# main.net
KiCad netlist of a schematic drawn in EAGLE
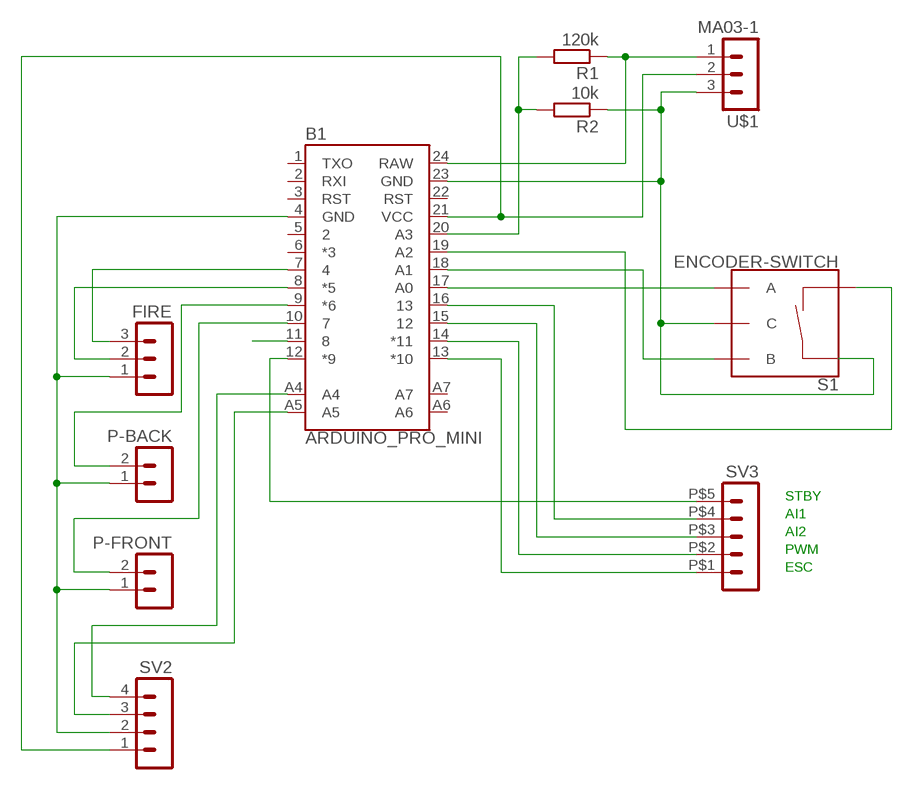
[diagram p0: schematic, sheet 1]

(export (version "E")
  (design (tool "Eeschema 10.0.6"))
  (components
    (comp (ref "B1")
      (value "ARDUINO_PRO_MINI")
      (footprint "eagle-import:ARDUINO_PRO_MINI_WO")
      (libsource (lib "eagle-import") (part "ARDUINO_PRO_MINI"))
    )
    (comp (ref "FIRE")
      (value "MA03-1")
      (footprint "eagle-import:MA03-1")
      (libsource (lib "eagle-import") (part "MA03-1"))
    )
    (comp (ref "P-BACK")
      (value "MA02-1")
      (footprint "eagle-import:MA02-1")
      (libsource (lib "eagle-import") (part "MA02-1"))
    )
    (comp (ref "P-FRONT")
      (value "MA02-1")
      (footprint "eagle-import:MA02-1")
      (libsource (lib "eagle-import") (part "MA02-1"))
    )
    (comp (ref "R1")
      (value "120k")
      (footprint "eagle-import:0204_5")
      (libsource (lib "eagle-import") (part "R-EU_0204/5"))
    )
    (comp (ref "R2")
      (value "10k")
      (footprint "eagle-import:0204V")
      (libsource (lib "eagle-import") (part "R-EU_0204/2V"))
    )
    (comp (ref "S1")
      (value "ENCODER-SWITCH")
      (footprint "eagle-import:ROTARY_ENC_PLAIN")
      (libsource (lib "eagle-import") (part "ENCODER-SWITCH"))
    )
    (comp (ref "SV2")
      (value "MA04-1")
      (footprint "eagle-import:MA04-1")
      (libsource (lib "eagle-import") (part "MA04-1"))
    )
    (comp (ref "SV3")
      (value "MA05-1")
      (footprint "eagle-import:MA05-1")
      (libsource (lib "eagle-import") (part "MA05-1"))
    )
    (comp (ref "U$1")
      (value "MA03-1")
      (footprint "eagle-import:MA03-1")
      (libsource (lib "eagle-import") (part "MA03-1"))
    )
  )
  (nets
    (net (code "1") (name "Net-(B1-*5)") (class "Default")
      (node (ref "B1") (pin "8") (pinfunction "*5_8") (pintype "bidirectional"))
      (node (ref "FIRE") (pin "2") (pinfunction "2_2") (pintype "passive"))
    )
    (net (code "2") (name "Net-(B1-*6)") (class "Default")
      (node (ref "B1") (pin "9") (pinfunction "*6_9") (pintype "bidirectional"))
      (node (ref "P-BACK") (pin "2") (pinfunction "3_2") (pintype "passive"))
    )
    (net (code "3") (name "Net-(B1-*9)") (class "Default")
      (node (ref "B1") (pin "12") (pinfunction "*9_12") (pintype "bidirectional"))
      (node (ref "SV3") (pin "P$5") (pinfunction "5_P$5") (pintype "passive"))
    )
    (net (code "4") (name "Net-(B1-*10)") (class "Default")
      (node (ref "B1") (pin "13") (pinfunction "*10_13") (pintype "bidirectional"))
      (node (ref "SV3") (pin "P$1") (pinfunction "1_P$1") (pintype "passive"))
    )
    (net (code "5") (name "Net-(B1-*11)") (class "Default")
      (node (ref "B1") (pin "14") (pinfunction "*11_14") (pintype "bidirectional"))
      (node (ref "SV3") (pin "P$2") (pinfunction "2_P$2") (pintype "passive"))
    )
    (net (code "6") (name "Net-(B1-4)") (class "Default")
      (node (ref "B1") (pin "7") (pinfunction "4_7") (pintype "bidirectional"))
      (node (ref "FIRE") (pin "3") (pinfunction "3_3") (pintype "passive"))
    )
    (net (code "7") (name "Net-(B1-7)") (class "Default")
      (node (ref "B1") (pin "10") (pinfunction "7_10") (pintype "bidirectional"))
      (node (ref "P-FRONT") (pin "2") (pinfunction "3_2") (pintype "passive"))
    )
    (net (code "8") (name "Net-(B1-12)") (class "Default")
      (node (ref "B1") (pin "15") (pinfunction "12_15") (pintype "bidirectional"))
      (node (ref "SV3") (pin "P$3") (pinfunction "3_P$3") (pintype "passive"))
    )
    (net (code "9") (name "Net-(B1-13)") (class "Default")
      (node (ref "B1") (pin "16") (pinfunction "13_16") (pintype "bidirectional"))
      (node (ref "SV3") (pin "P$4") (pinfunction "4_P$4") (pintype "passive"))
    )
    (net (code "10") (name "Net-(B1-A0)") (class "Default")
      (node (ref "B1") (pin "17") (pinfunction "A0_17") (pintype "bidirectional"))
      (node (ref "S1") (pin "A") (pinfunction "A_A") (pintype "bidirectional"))
    )
    (net (code "11") (name "Net-(B1-A1)") (class "Default")
      (node (ref "B1") (pin "18") (pinfunction "A1_18") (pintype "bidirectional"))
      (node (ref "S1") (pin "B") (pinfunction "B_B") (pintype "bidirectional"))
    )
    (net (code "12") (name "Net-(B1-A2)") (class "Default")
      (node (ref "B1") (pin "19") (pinfunction "A2_19") (pintype "bidirectional"))
      (node (ref "S1") (pin "SW-") (pinfunction "SW-_SW-") (pintype "bidirectional"))
    )
    (net (code "13") (name "Net-(B1-A3)") (class "Default")
      (node (ref "B1") (pin "20") (pinfunction "A3_20") (pintype "bidirectional"))
      (node (ref "R1") (pin "2") (pinfunction "2_2") (pintype "passive"))
      (node (ref "R2") (pin "2") (pinfunction "2_2") (pintype "passive"))
    )
    (net (code "14") (name "Net-(B1-GND-Pad23)") (class "Default")
      (node (ref "B1") (pin "23") (pinfunction "GND_23") (pintype "power_in"))
      (node (ref "R2") (pin "1") (pinfunction "1_1") (pintype "passive"))
      (node (ref "S1") (pin "C") (pinfunction "C_C") (pintype "bidirectional"))
      (node (ref "U$1") (pin "3") (pinfunction "3_3") (pintype "passive"))
    )
    (net (code "15") (name "Net-(B1-PadA4)") (class "Default")
      (node (ref "B1") (pin "A4") (pinfunction "A4_A4") (pintype "bidirectional"))
      (node (ref "SV2") (pin "4") (pinfunction "4_4") (pintype "passive"))
    )
    (net (code "16") (name "Net-(B1-PadA5)") (class "Default")
      (node (ref "B1") (pin "A5") (pinfunction "A5_A5") (pintype "bidirectional"))
      (node (ref "SV2") (pin "3") (pinfunction "3_3") (pintype "passive"))
    )
    (net (code "17") (name "Net-(B1-RAW)") (class "Default")
      (node (ref "B1") (pin "24") (pinfunction "RAW_24") (pintype "power_in"))
      (node (ref "R1") (pin "1") (pinfunction "1_1") (pintype "passive"))
      (node (ref "U$1") (pin "1") (pinfunction "1_1") (pintype "passive"))
    )
    (net (code "18") (name "Net-(B1-VCC)") (class "Default")
      (node (ref "B1") (pin "21") (pinfunction "VCC_21") (pintype "power_in"))
      (node (ref "SV2") (pin "1") (pinfunction "1_1") (pintype "passive"))
      (node (ref "U$1") (pin "2") (pinfunction "2_2") (pintype "passive"))
    )
    (net (code "19") (name "Net-(P-BACK-2)") (class "Default")
      (node (ref "B1") (pin "4") (pinfunction "GND_4") (pintype "power_in"))
      (node (ref "FIRE") (pin "1") (pinfunction "1_1") (pintype "passive"))
      (node (ref "P-BACK") (pin "1") (pinfunction "2_1") (pintype "passive"))
      (node (ref "P-FRONT") (pin "1") (pinfunction "2_1") (pintype "passive"))
      (node (ref "SV2") (pin "2") (pinfunction "2_2") (pintype "passive"))
    )
    (net (code "20") (name "unconnected-(B1-*3-Pad6)") (class "Default")
      (node (ref "B1") (pin "6") (pinfunction "*3_6") (pintype "bidirectional"))
    )
    (net (code "21") (name "unconnected-(B1-2-Pad5)") (class "Default")
      (node (ref "B1") (pin "5") (pinfunction "2_5") (pintype "bidirectional"))
    )
    (net (code "22") (name "unconnected-(B1-8-Pad11)") (class "Default")
      (node (ref "B1") (pin "11") (pinfunction "8_11") (pintype "bidirectional"))
    )
    (net (code "23") (name "unconnected-(B1-PadA6)") (class "Default")
      (node (ref "B1") (pin "A6") (pinfunction "A6_A6") (pintype "bidirectional"))
    )
    (net (code "24") (name "unconnected-(B1-PadA7)") (class "Default")
      (node (ref "B1") (pin "A7") (pinfunction "A7_A7") (pintype "bidirectional"))
    )
    (net (code "25") (name "unconnected-(B1-RST-Pad3)") (class "Default")
      (node (ref "B1") (pin "3") (pinfunction "RST_3") (pintype "bidirectional"))
    )
    (net (code "26") (name "unconnected-(B1-RST-Pad22)") (class "Default")
      (node (ref "B1") (pin "22") (pinfunction "RST_22") (pintype "bidirectional"))
    )
    (net (code "27") (name "unconnected-(B1-RXI-Pad2)") (class "Default")
      (node (ref "B1") (pin "2") (pinfunction "RXI_2") (pintype "bidirectional"))
    )
    (net (code "28") (name "unconnected-(B1-TXO-Pad1)") (class "Default")
      (node (ref "B1") (pin "1") (pinfunction "TXO_1") (pintype "bidirectional"))
    )
    (net (code "29") (name "unconnected-(S1-PadSW+)") (class "Default")
      (node (ref "S1") (pin "SW+") (pinfunction "SW+_SW+") (pintype "bidirectional"))
    )
  )
)
